# card.net
KiCad netlist of a schematic drawn in Altium Designer
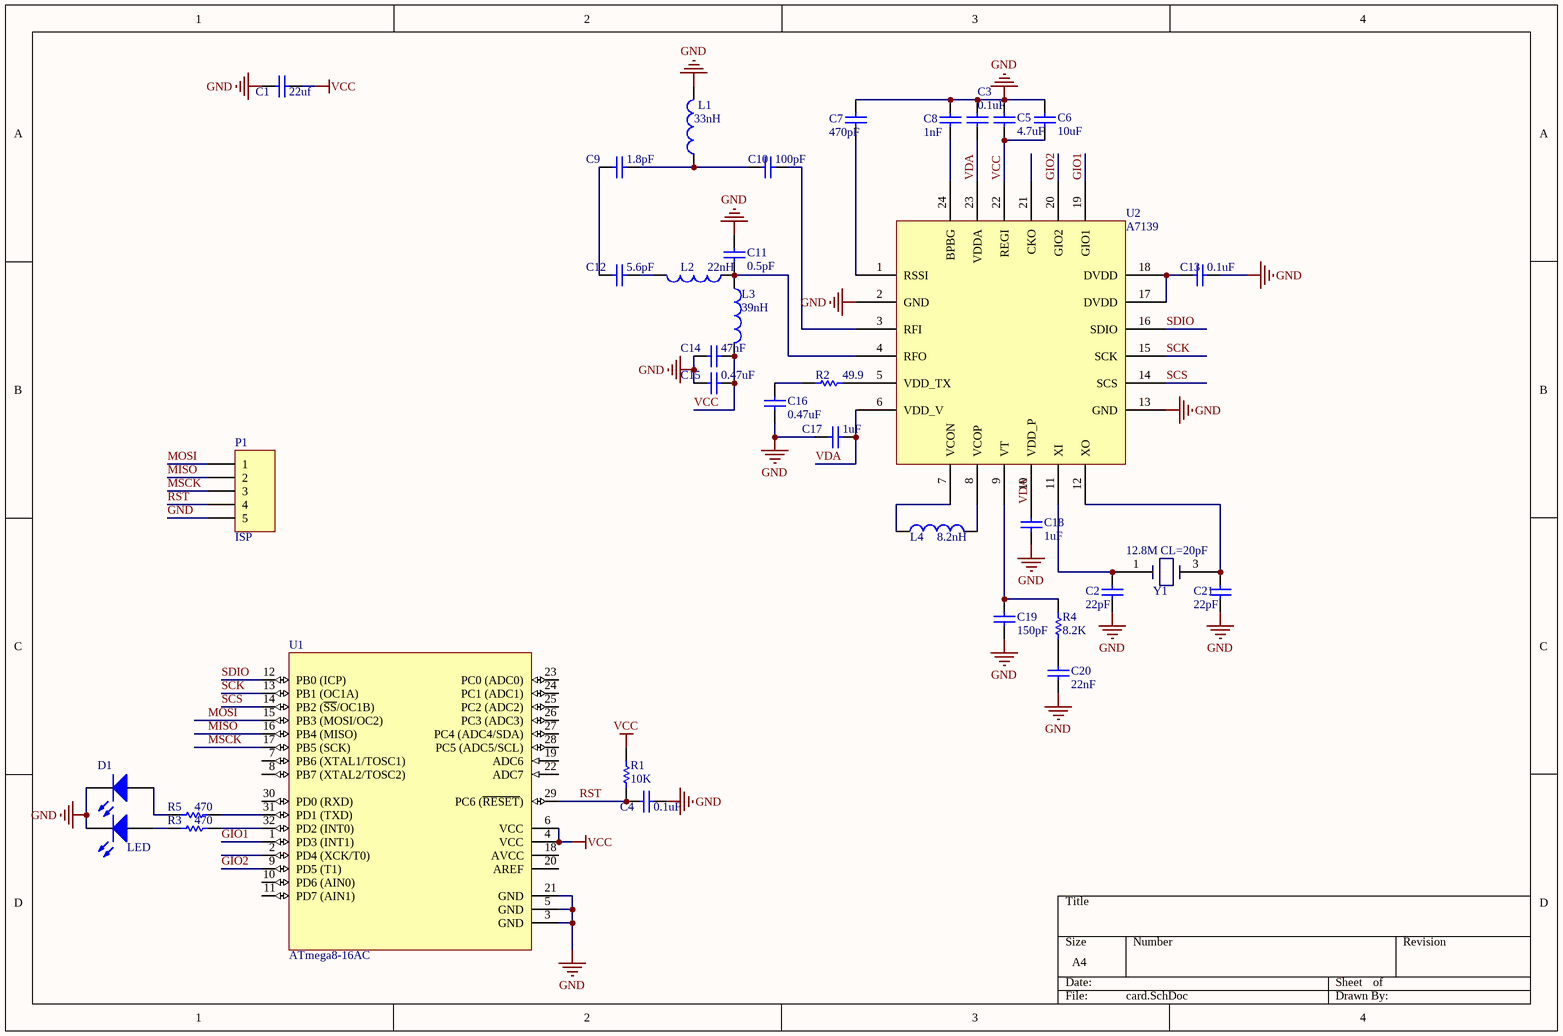
[diagram p0: card.SchDoc]

(export (version "E")
  (design (tool "Eeschema 10.0.6"))
  (components
    (comp (ref "C1")
      (value "22uf")
      (footprint "3216[1206]")
      (description "Capacitor")
      (fields (field (name "Comment") "Cap") (field (name "PUBLISHER") "Altium Limited"))
      (libsource (lib "Miscellaneous Devices") (part "Cap"))
    )
    (comp (ref "C2")
      (value "22pF")
      (footprint "0402-A")
      (description "Capacitor")
      (fields (field (name "Comment") "Cap") (field (name "PUBLISHER") "Altium Limited"))
      (libsource (lib "Miscellaneous Devices") (part "Cap"))
    )
    (comp (ref "C3")
      (value "0.1uF")
      (footprint "0402-A")
      (description "Capacitor")
      (fields (field (name "Comment") "Cap") (field (name "PUBLISHER") "Altium Limited"))
      (libsource (lib "Miscellaneous Devices") (part "Cap"))
    )
    (comp (ref "C4")
      (value "0.1uF")
      (footprint "0603")
      (description "Capacitor")
      (fields (field (name "Comment") "Cap") (field (name "PUBLISHER") "Altium Limited"))
      (libsource (lib "Miscellaneous Devices") (part "Cap"))
    )
    (comp (ref "C5")
      (value "4.7uF")
      (footprint "0603")
      (description "Capacitor")
      (fields (field (name "Comment") "Cap") (field (name "PUBLISHER") "Altium Limited"))
      (libsource (lib "Miscellaneous Devices") (part "Cap"))
    )
    (comp (ref "C6")
      (value "10uF")
      (footprint "0603")
      (description "Capacitor")
      (fields (field (name "Comment") "Cap") (field (name "PUBLISHER") "Altium Limited"))
      (libsource (lib "Miscellaneous Devices") (part "Cap"))
    )
    (comp (ref "C7")
      (value "470pF")
      (footprint "0402-A")
      (description "Capacitor")
      (fields (field (name "Comment") "Cap") (field (name "PUBLISHER") "Altium Limited"))
      (libsource (lib "Miscellaneous Devices") (part "Cap"))
    )
    (comp (ref "C8")
      (value "1nF")
      (footprint "0402-A")
      (description "Capacitor")
      (fields (field (name "Comment") "Cap") (field (name "PUBLISHER") "Altium Limited"))
      (libsource (lib "Miscellaneous Devices") (part "Cap"))
    )
    (comp (ref "C9")
      (value "1.8pF")
      (footprint "0402-A")
      (description "Capacitor")
      (fields (field (name "Comment") "Cap") (field (name "PUBLISHER") "Altium Limited"))
      (libsource (lib "Miscellaneous Devices") (part "Cap"))
    )
    (comp (ref "C10")
      (value "100pF")
      (footprint "0402-A")
      (description "Capacitor")
      (fields (field (name "Comment") "Cap") (field (name "PUBLISHER") "Altium Limited"))
      (libsource (lib "Miscellaneous Devices") (part "Cap"))
    )
    (comp (ref "C11")
      (value "0.5pF")
      (footprint "0402-A")
      (description "Capacitor")
      (fields (field (name "Comment") "Cap") (field (name "PUBLISHER") "Altium Limited"))
      (libsource (lib "Miscellaneous Devices") (part "Cap"))
    )
    (comp (ref "C12")
      (value "5.6pF")
      (footprint "0402-A")
      (description "Capacitor")
      (fields (field (name "Comment") "Cap") (field (name "PUBLISHER") "Altium Limited"))
      (libsource (lib "Miscellaneous Devices") (part "Cap"))
    )
    (comp (ref "C13")
      (value "0.1uF")
      (footprint "0402-A")
      (description "Capacitor")
      (fields (field (name "Comment") "Cap") (field (name "PUBLISHER") "Altium Limited"))
      (libsource (lib "Miscellaneous Devices") (part "Cap"))
    )
    (comp (ref "C14")
      (value "47nF")
      (footprint "0402-A")
      (description "Capacitor")
      (fields (field (name "Comment") "Cap") (field (name "PUBLISHER") "Altium Limited"))
      (libsource (lib "Miscellaneous Devices") (part "Cap"))
    )
    (comp (ref "C15")
      (value "0.47uF")
      (footprint "0402-A")
      (description "Capacitor")
      (fields (field (name "Comment") "Cap") (field (name "PUBLISHER") "Altium Limited"))
      (libsource (lib "Miscellaneous Devices") (part "Cap"))
    )
    (comp (ref "C16")
      (value "0.47uF")
      (footprint "0402-A")
      (description "Capacitor")
      (fields (field (name "Comment") "Cap") (field (name "PUBLISHER") "Altium Limited"))
      (libsource (lib "Miscellaneous Devices") (part "Cap"))
    )
    (comp (ref "C17")
      (value "1uF")
      (footprint "0402-A")
      (description "Capacitor")
      (fields (field (name "Comment") "Cap") (field (name "PUBLISHER") "Altium Limited"))
      (libsource (lib "Miscellaneous Devices") (part "Cap"))
    )
    (comp (ref "C18")
      (value "1uF")
      (footprint "0402-A")
      (description "Capacitor")
      (fields (field (name "Comment") "Cap") (field (name "PUBLISHER") "Altium Limited"))
      (libsource (lib "Miscellaneous Devices") (part "Cap"))
    )
    (comp (ref "C19")
      (value "150pF")
      (footprint "0402-A")
      (description "Capacitor")
      (fields (field (name "Comment") "Cap") (field (name "PUBLISHER") "Altium Limited"))
      (libsource (lib "Miscellaneous Devices") (part "Cap"))
    )
    (comp (ref "C20")
      (value "22nF")
      (footprint "0402-A")
      (description "Capacitor")
      (fields (field (name "Comment") "Cap") (field (name "PUBLISHER") "Altium Limited"))
      (libsource (lib "Miscellaneous Devices") (part "Cap"))
    )
    (comp (ref "C21")
      (value "22pF")
      (footprint "0402-A")
      (description "Capacitor")
      (fields (field (name "Comment") "Cap") (field (name "PUBLISHER") "Altium Limited"))
      (libsource (lib "Miscellaneous Devices") (part "Cap"))
    )
    (comp (ref "D1") (value "LED") (footprint "0603-LED-DOUBLE") (libsource (lib "Tank") (part "LED-DOUBLE")))
    (comp (ref "L1")
      (value "33nH")
      (footprint "0603")
      (description "Inductor")
      (fields (field (name "PUBLISHER") "Altium Limited"))
      (libsource (lib "Miscellaneous Devices") (part "Inductor"))
    )
    (comp (ref "L2")
      (value "22nH")
      (footprint "0603")
      (description "Inductor")
      (fields (field (name "PUBLISHER") "Altium Limited"))
      (libsource (lib "Miscellaneous Devices") (part "Inductor"))
    )
    (comp (ref "L3")
      (value "39nH")
      (footprint "0603")
      (description "Inductor")
      (fields (field (name "PUBLISHER") "Altium Limited"))
      (libsource (lib "Miscellaneous Devices") (part "Inductor"))
    )
    (comp (ref "L4")
      (value "8.2nH")
      (footprint "0402-A")
      (description "Inductor")
      (fields (field (name "PUBLISHER") "Altium Limited"))
      (libsource (lib "Miscellaneous Devices") (part "Inductor"))
    )
    (comp (ref "P1")
      (value "ISP")
      (footprint "HDR1X5")
      (description "Header, 5-Pin")
      (fields (field (name "PUBLISHER") "Altium Limited"))
      (libsource (lib "Miscellaneous Connectors") (part "Header 5"))
    )
    (comp (ref "R1")
      (value "10K")
      (footprint "0603")
      (description "Resistor")
      (fields (field (name "Comment") "Res1") (field (name "PUBLISHER") "Altium Limited"))
      (libsource (lib "Miscellaneous Devices") (part "Res1"))
    )
    (comp (ref "R2")
      (value "49.9")
      (footprint "0402-A")
      (description "Resistor")
      (fields (field (name "Comment") "Res1") (field (name "PUBLISHER") "Altium Limited"))
      (libsource (lib "Miscellaneous Devices") (part "Res1"))
    )
    (comp (ref "R3")
      (value "470")
      (footprint "0603")
      (description "Resistor")
      (fields (field (name "Comment") "Res1") (field (name "PUBLISHER") "Altium Limited"))
      (libsource (lib "Miscellaneous Devices") (part "Res1"))
    )
    (comp (ref "R4")
      (value "8.2K")
      (footprint "0402-A")
      (description "Resistor")
      (fields (field (name "Comment") "Res1") (field (name "PUBLISHER") "Altium Limited"))
      (libsource (lib "Miscellaneous Devices") (part "Res1"))
    )
    (comp (ref "R5")
      (value "470")
      (footprint "0603")
      (description "Resistor")
      (fields (field (name "Comment") "Res1") (field (name "PUBLISHER") "Altium Limited"))
      (libsource (lib "Miscellaneous Devices") (part "Res1"))
    )
    (comp (ref "U1")
      (value "ATmega8-16AC")
      (footprint "Atmel Footprints:32A_M")
      (description "8-Bit AVR Microcontroller with 8K Bytes of In-System Programmable Flash Memory")
      (fields (field (name "PUBLISHER") "Altium Limited"))
      (libsource (lib "Atmel Microcontroller 8-Bit AVR") (part "ATmega8-16AC"))
    )
    (comp (ref "U2") (value "A7139") (footprint "QFN24N") (libsource (lib "TANK") (part "A7139")))
    (comp (ref "Y1") (value "12.8M CL=20pF") (libsource (lib "TANK") (part "3225-wy")))
  )
  (nets
    (net (code "1") (name "/GIO1") (class "Default")
      (node (ref "U1") (pin "1") (pinfunction "PD3_(INT1)_1") (pintype "bidirectional"))
      (node (ref "U2") (pin "19") (pinfunction "GIO1_19") (pintype "passive"))
    )
    (net (code "2") (name "/GIO2") (class "Default")
      (node (ref "U1") (pin "9") (pinfunction "PD5_(T1)_9") (pintype "bidirectional"))
      (node (ref "U2") (pin "20") (pinfunction "GIO2_20") (pintype "passive"))
    )
    (net (code "3") (name "/MISO") (class "Default")
      (node (ref "P1") (pin "2") (pinfunction "2_2") (pintype "passive"))
      (node (ref "U1") (pin "16") (pinfunction "PB4_(MISO)_16") (pintype "bidirectional"))
    )
    (net (code "4") (name "/MOSI") (class "Default")
      (node (ref "P1") (pin "1") (pinfunction "1_1") (pintype "passive"))
      (node (ref "U1") (pin "15") (pinfunction "PB3_(MOSI/OC2)_15") (pintype "bidirectional"))
    )
    (net (code "5") (name "/MSCK") (class "Default")
      (node (ref "P1") (pin "3") (pinfunction "3_3") (pintype "passive"))
      (node (ref "U1") (pin "17") (pinfunction "PB5_(SCK)_17") (pintype "bidirectional"))
    )
    (net (code "6") (name "/RST") (class "Default")
      (node (ref "C4") (pin "1") (pinfunction "1_1") (pintype "passive"))
      (node (ref "P1") (pin "4") (pinfunction "4_4") (pintype "passive"))
      (node (ref "R1") (pin "1") (pinfunction "1_1") (pintype "passive"))
      (node (ref "U1") (pin "29") (pinfunction "PC6_(~{RESET})_29") (pintype "bidirectional"))
    )
    (net (code "7") (name "/SCK") (class "Default")
      (node (ref "U1") (pin "13") (pinfunction "PB1_(OC1A)_13") (pintype "bidirectional"))
      (node (ref "U2") (pin "15") (pinfunction "SCK_15") (pintype "passive"))
    )
    (net (code "8") (name "/SCS") (class "Default")
      (node (ref "U1") (pin "14") (pinfunction "PB2_(~{SS}/OC1B)_14") (pintype "bidirectional"))
      (node (ref "U2") (pin "14") (pinfunction "SCS_14") (pintype "passive"))
    )
    (net (code "9") (name "/SDIO") (class "Default")
      (node (ref "U1") (pin "12") (pinfunction "PB0_(ICP)_12") (pintype "bidirectional"))
      (node (ref "U2") (pin "16") (pinfunction "SDIO_16") (pintype "passive"))
    )
    (net (code "10") (name "/VDA") (class "Default")
      (node (ref "C17") (pin "1") (pinfunction "1_1") (pintype "passive"))
      (node (ref "C18") (pin "2") (pinfunction "2_2") (pintype "passive"))
      (node (ref "C3") (pin "1") (pinfunction "1_1") (pintype "passive"))
      (node (ref "U2") (pin "10") (pinfunction "VDD_P_10") (pintype "passive"))
      (node (ref "U2") (pin "23") (pinfunction "VDDA_23") (pintype "passive"))
      (node (ref "U2") (pin "6") (pinfunction "VDD_V_6") (pintype "passive"))
    )
    (net (code "11") (name "GND") (class "Default")
      (node (ref "C1") (pin "1") (pinfunction "1_1") (pintype "passive"))
      (node (ref "C11") (pin "1") (pinfunction "1_1") (pintype "passive"))
      (node (ref "C13") (pin "2") (pinfunction "2_2") (pintype "passive"))
      (node (ref "C14") (pin "2") (pinfunction "2_2") (pintype "passive"))
      (node (ref "C15") (pin "2") (pinfunction "2_2") (pintype "passive"))
      (node (ref "C16") (pin "1") (pinfunction "1_1") (pintype "passive"))
      (node (ref "C17") (pin "2") (pinfunction "2_2") (pintype "passive"))
      (node (ref "C18") (pin "1") (pinfunction "1_1") (pintype "passive"))
      (node (ref "C19") (pin "1") (pinfunction "1_1") (pintype "passive"))
      (node (ref "C2") (pin "1") (pinfunction "1_1") (pintype "passive"))
      (node (ref "C20") (pin "1") (pinfunction "1_1") (pintype "passive"))
      (node (ref "C21") (pin "1") (pinfunction "1_1") (pintype "passive"))
      (node (ref "C3") (pin "2") (pinfunction "2_2") (pintype "passive"))
      (node (ref "C4") (pin "2") (pinfunction "2_2") (pintype "passive"))
      (node (ref "C5") (pin "2") (pinfunction "2_2") (pintype "passive"))
      (node (ref "C6") (pin "2") (pinfunction "2_2") (pintype "passive"))
      (node (ref "C7") (pin "2") (pinfunction "2_2") (pintype "passive"))
      (node (ref "C8") (pin "2") (pinfunction "2_2") (pintype "passive"))
      (node (ref "D1") (pin "3") (pinfunction "K_3") (pintype "passive"))
      (node (ref "D1") (pin "4") (pinfunction "K_4") (pintype "passive"))
      (node (ref "L1") (pin "2") (pinfunction "2_2") (pintype "passive"))
      (node (ref "P1") (pin "5") (pinfunction "5_5") (pintype "passive"))
      (node (ref "U1") (pin "21") (pinfunction "GND_21") (pintype "power_in"))
      (node (ref "U1") (pin "3") (pinfunction "GND_3") (pintype "power_in"))
      (node (ref "U1") (pin "5") (pinfunction "GND_5") (pintype "power_in"))
      (node (ref "U2") (pin "13") (pinfunction "GND_13") (pintype "passive"))
      (node (ref "U2") (pin "2") (pinfunction "GND_2") (pintype "passive"))
      (node (ref "U2") (pin "25") (pinfunction "GND_25") (pintype "power_in"))
    )
    (net (code "12") (name "Net-(C10-Pad2)") (class "Default")
      (node (ref "C10") (pin "2") (pinfunction "2_2") (pintype "passive"))
      (node (ref "C9") (pin "1") (pinfunction "1_1") (pintype "passive"))
      (node (ref "L1") (pin "1") (pinfunction "1_1") (pintype "passive"))
    )
    (net (code "13") (name "Net-(C12-Pad1)") (class "Default")
      (node (ref "C12") (pin "1") (pinfunction "1_1") (pintype "passive"))
      (node (ref "L2") (pin "2") (pinfunction "2_2") (pintype "passive"))
    )
    (net (code "14") (name "Net-(C12-Pad2)") (class "Default")
      (node (ref "C12") (pin "2") (pinfunction "2_2") (pintype "passive"))
      (node (ref "C9") (pin "2") (pinfunction "2_2") (pintype "passive"))
    )
    (net (code "15") (name "Net-(C13-Pad1)") (class "Default")
      (node (ref "C13") (pin "1") (pinfunction "1_1") (pintype "passive"))
      (node (ref "U2") (pin "17") (pinfunction "DVDD_17") (pintype "passive"))
      (node (ref "U2") (pin "18") (pinfunction "DVDD_18") (pintype "passive"))
    )
    (net (code "16") (name "Net-(C16-Pad2)") (class "Default")
      (node (ref "C16") (pin "2") (pinfunction "2_2") (pintype "passive"))
      (node (ref "R2") (pin "2") (pinfunction "2_2") (pintype "passive"))
    )
    (net (code "17") (name "Net-(C20-Pad2)") (class "Default")
      (node (ref "C20") (pin "2") (pinfunction "2_2") (pintype "passive"))
      (node (ref "R4") (pin "1") (pinfunction "1_1") (pintype "passive"))
    )
    (net (code "18") (name "Net-(D1-A-Pad1)") (class "Default")
      (node (ref "D1") (pin "1") (pinfunction "A_1") (pintype "passive"))
      (node (ref "R3") (pin "2") (pinfunction "2_2") (pintype "passive"))
    )
    (net (code "19") (name "Net-(D1-A-Pad2)") (class "Default")
      (node (ref "D1") (pin "2") (pinfunction "A_2") (pintype "passive"))
      (node (ref "R5") (pin "2") (pinfunction "2_2") (pintype "passive"))
    )
    (net (code "20") (name "Net-(U1-PD1_(TXD))") (class "Default")
      (node (ref "R5") (pin "1") (pinfunction "1_1") (pintype "passive"))
      (node (ref "U1") (pin "31") (pinfunction "PD1_(TXD)_31") (pintype "bidirectional"))
    )
    (net (code "21") (name "Net-(U1-PD2_(INT0))") (class "Default")
      (node (ref "R3") (pin "1") (pinfunction "1_1") (pintype "passive"))
      (node (ref "U1") (pin "32") (pinfunction "PD2_(INT0)_32") (pintype "bidirectional"))
    )
    (net (code "22") (name "Net-(U2-BPBG)") (class "Default")
      (node (ref "C8") (pin "1") (pinfunction "1_1") (pintype "passive"))
      (node (ref "U2") (pin "24") (pinfunction "BPBG_24") (pintype "passive"))
    )
    (net (code "23") (name "Net-(U2-RFI)") (class "Default")
      (node (ref "C10") (pin "1") (pinfunction "1_1") (pintype "passive"))
      (node (ref "U2") (pin "3") (pinfunction "RFI_3") (pintype "passive"))
    )
    (net (code "24") (name "Net-(U2-RFO)") (class "Default")
      (node (ref "C11") (pin "2") (pinfunction "2_2") (pintype "passive"))
      (node (ref "L2") (pin "1") (pinfunction "1_1") (pintype "passive"))
      (node (ref "L3") (pin "1") (pinfunction "1_1") (pintype "passive"))
      (node (ref "U2") (pin "4") (pinfunction "RFO_4") (pintype "passive"))
    )
    (net (code "25") (name "Net-(U2-RSSI)") (class "Default")
      (node (ref "C7") (pin "1") (pinfunction "1_1") (pintype "passive"))
      (node (ref "U2") (pin "1") (pinfunction "RSSI_1") (pintype "passive"))
    )
    (net (code "26") (name "Net-(U2-VCON)") (class "Default")
      (node (ref "L4") (pin "1") (pinfunction "1_1") (pintype "passive"))
      (node (ref "U2") (pin "7") (pinfunction "VCON_7") (pintype "passive"))
    )
    (net (code "27") (name "Net-(U2-VCOP)") (class "Default")
      (node (ref "L4") (pin "2") (pinfunction "2_2") (pintype "passive"))
      (node (ref "U2") (pin "8") (pinfunction "VCOP_8") (pintype "passive"))
    )
    (net (code "28") (name "Net-(U2-VDD_TX)") (class "Default")
      (node (ref "R2") (pin "1") (pinfunction "1_1") (pintype "passive"))
      (node (ref "U2") (pin "5") (pinfunction "VDD_TX_5") (pintype "passive"))
    )
    (net (code "29") (name "Net-(U2-VT)") (class "Default")
      (node (ref "C19") (pin "2") (pinfunction "2_2") (pintype "passive"))
      (node (ref "R4") (pin "2") (pinfunction "2_2") (pintype "passive"))
      (node (ref "U2") (pin "9") (pinfunction "VT_9") (pintype "passive"))
    )
    (net (code "30") (name "Net-(U2-XI)") (class "Default")
      (node (ref "C2") (pin "2") (pinfunction "2_2") (pintype "passive"))
      (node (ref "U2") (pin "11") (pinfunction "XI_11") (pintype "passive"))
      (node (ref "Y1") (pin "1") (pinfunction "1_1") (pintype "passive"))
    )
    (net (code "31") (name "Net-(U2-XO)") (class "Default")
      (node (ref "C21") (pin "2") (pinfunction "2_2") (pintype "passive"))
      (node (ref "U2") (pin "12") (pinfunction "XO_12") (pintype "passive"))
      (node (ref "Y1") (pin "3") (pinfunction "3_3") (pintype "passive"))
    )
    (net (code "32") (name "VCC") (class "Default")
      (node (ref "C1") (pin "2") (pinfunction "2_2") (pintype "passive"))
      (node (ref "C14") (pin "1") (pinfunction "1_1") (pintype "passive"))
      (node (ref "C15") (pin "1") (pinfunction "1_1") (pintype "passive"))
      (node (ref "C5") (pin "1") (pinfunction "1_1") (pintype "passive"))
      (node (ref "C6") (pin "1") (pinfunction "1_1") (pintype "passive"))
      (node (ref "L3") (pin "2") (pinfunction "2_2") (pintype "passive"))
      (node (ref "R1") (pin "2") (pinfunction "2_2") (pintype "passive"))
      (node (ref "U1") (pin "4") (pinfunction "VCC_4") (pintype "power_in"))
      (node (ref "U1") (pin "6") (pinfunction "VCC_6") (pintype "power_in"))
      (node (ref "U2") (pin "22") (pinfunction "REGI_22") (pintype "passive"))
    )
    (net (code "33") (name "unconnected-(U1-ADC6-Pad19)") (class "Default")
      (node (ref "U1") (pin "19") (pinfunction "ADC6_19") (pintype "input"))
    )
    (net (code "34") (name "unconnected-(U1-ADC7-Pad22)") (class "Default")
      (node (ref "U1") (pin "22") (pinfunction "ADC7_22") (pintype "input"))
    )
    (net (code "35") (name "unconnected-(U1-AREF-Pad20)") (class "Default")
      (node (ref "U1") (pin "20") (pinfunction "AREF_20") (pintype "passive"))
    )
    (net (code "36") (name "unconnected-(U1-AVCC-Pad18)") (class "Default")
      (node (ref "U1") (pin "18") (pinfunction "AVCC_18") (pintype "power_in"))
    )
    (net (code "37") (name "unconnected-(U1-PB6_(XTAL1{slash}TOSC1)-Pad7)") (class "Default")
      (node (ref "U1") (pin "7") (pinfunction "PB6_(XTAL1/TOSC1)_7") (pintype "bidirectional"))
    )
    (net (code "38") (name "unconnected-(U1-PB7_(XTAL2{slash}TOSC2)-Pad8)") (class "Default")
      (node (ref "U1") (pin "8") (pinfunction "PB7_(XTAL2/TOSC2)_8") (pintype "bidirectional"))
    )
    (net (code "39") (name "unconnected-(U1-PC0_(ADC0)-Pad23)") (class "Default")
      (node (ref "U1") (pin "23") (pinfunction "PC0_(ADC0)_23") (pintype "bidirectional"))
    )
    (net (code "40") (name "unconnected-(U1-PC1_(ADC1)-Pad24)") (class "Default")
      (node (ref "U1") (pin "24") (pinfunction "PC1_(ADC1)_24") (pintype "bidirectional"))
    )
    (net (code "41") (name "unconnected-(U1-PC2_(ADC2)-Pad25)") (class "Default")
      (node (ref "U1") (pin "25") (pinfunction "PC2_(ADC2)_25") (pintype "bidirectional"))
    )
    (net (code "42") (name "unconnected-(U1-PC3_(ADC3)-Pad26)") (class "Default")
      (node (ref "U1") (pin "26") (pinfunction "PC3_(ADC3)_26") (pintype "bidirectional"))
    )
    (net (code "43") (name "unconnected-(U1-PC4_(ADC4{slash}SDA)-Pad27)") (class "Default")
      (node (ref "U1") (pin "27") (pinfunction "PC4_(ADC4/SDA)_27") (pintype "bidirectional"))
    )
    (net (code "44") (name "unconnected-(U1-PC5_(ADC5{slash}SCL)-Pad28)") (class "Default")
      (node (ref "U1") (pin "28") (pinfunction "PC5_(ADC5/SCL)_28") (pintype "bidirectional"))
    )
    (net (code "45") (name "unconnected-(U1-PD0_(RXD)-Pad30)") (class "Default")
      (node (ref "U1") (pin "30") (pinfunction "PD0_(RXD)_30") (pintype "bidirectional"))
    )
    (net (code "46") (name "unconnected-(U1-PD4_(XCK{slash}T0)-Pad2)") (class "Default")
      (node (ref "U1") (pin "2") (pinfunction "PD4_(XCK/T0)_2") (pintype "bidirectional"))
    )
    (net (code "47") (name "unconnected-(U1-PD6_(AIN0)-Pad10)") (class "Default")
      (node (ref "U1") (pin "10") (pinfunction "PD6_(AIN0)_10") (pintype "bidirectional"))
    )
    (net (code "48") (name "unconnected-(U1-PD7_(AIN1)-Pad11)") (class "Default")
      (node (ref "U1") (pin "11") (pinfunction "PD7_(AIN1)_11") (pintype "bidirectional"))
    )
    (net (code "49") (name "unconnected-(U2-CKO-Pad21)") (class "Default")
      (node (ref "U2") (pin "21") (pinfunction "CKO_21") (pintype "passive"))
    )
  )
)
